# Sheet2.net
KiCad netlist of a schematic drawn in Altium Designer
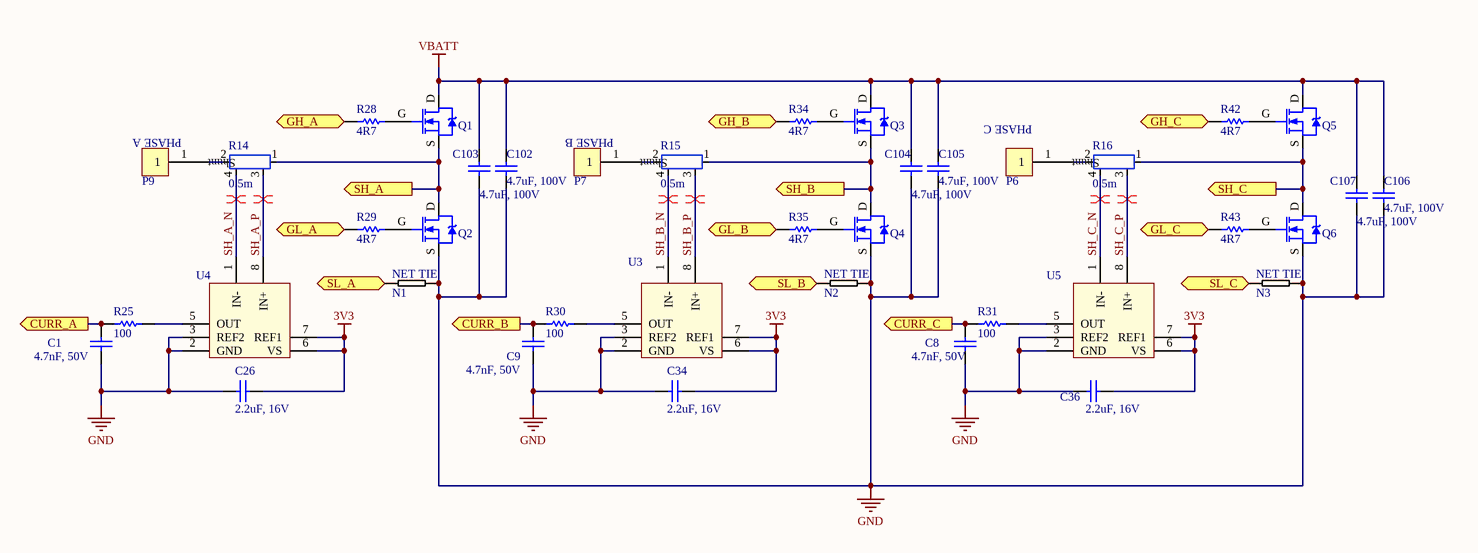
[diagram p0: Sheet2.SchDoc]

(export (version "E")
  (design (tool "Eeschema 10.0.6"))
  (components
    (comp (ref "C1")
      (value "4.7nF, 50V")
      (footprint "SMD-0603 Capacitor")
      (description "CAP 4.7n, 50V, 0603")
      (fields
        (field (name "MANUFACTURER PART NUMBER") "GRM39X472J50D")
        (field (name "MANUFACTURER") "Murata Electronics North America")
      )
      (libsource (lib "Master Data Link") (part "CAP"))
    )
    (comp (ref "C8")
      (value "4.7nF, 50V")
      (footprint "SMD-0603 Capacitor")
      (description "CAP 4.7n, 50V, 0603")
      (fields
        (field (name "MANUFACTURER PART NUMBER") "GRM39X472J50D")
        (field (name "MANUFACTURER") "Murata Electronics North America")
      )
      (libsource (lib "Master Data Link") (part "CAP"))
    )
    (comp (ref "C9")
      (value "4.7nF, 50V")
      (footprint "SMD-0603 Capacitor")
      (description "CAP 4.7n, 50V, 0603")
      (fields
        (field (name "MANUFACTURER PART NUMBER") "GRM39X472J50D")
        (field (name "MANUFACTURER") "Murata Electronics North America")
      )
      (libsource (lib "Master Data Link") (part "CAP"))
    )
    (comp (ref "C26")
      (value "2.2uF, 16V")
      (footprint "SMD-0603 Capacitor")
      (description "CAP 2.2u, 16V, 0603")
      (fields
        (field (name "MANUFACTURER PART NUMBER") "C1608X5R1C225M")
        (field (name "MANUFACTURER") "TDK Corporation")
      )
      (libsource (lib "Master Data Link") (part "CAP"))
    )
    (comp (ref "C34")
      (value "2.2uF, 16V")
      (footprint "SMD-0603 Capacitor")
      (description "CAP 2.2u, 16V, 0603")
      (fields
        (field (name "MANUFACTURER PART NUMBER") "C1608X5R1C225M")
        (field (name "MANUFACTURER") "TDK Corporation")
      )
      (libsource (lib "Master Data Link") (part "CAP"))
    )
    (comp (ref "C36")
      (value "2.2uF, 16V")
      (footprint "SMD-0603 Capacitor")
      (description "CAP 2.2u, 16V, 0603")
      (fields
        (field (name "MANUFACTURER PART NUMBER") "C1608X5R1C225M")
        (field (name "MANUFACTURER") "TDK Corporation")
      )
      (libsource (lib "Master Data Link") (part "CAP"))
    )
    (comp (ref "C102")
      (value "4.7uF, 100V")
      (footprint "SMD-1206 Capacitor")
      (description "4.7µF 100V Ceramic Capacitor X7S 1206")
      (fields
        (field (name "MANUFACTURER PART NUMBER") "12061Z475MAT2A")
        (field (name "MANUFACTURER") "AVX Corporation")
      )
      (libsource (lib "Master Data Link") (part "CAP"))
    )
    (comp (ref "C103")
      (value "4.7uF, 100V")
      (footprint "SMD-1206 Capacitor")
      (description "4.7µF 100V Ceramic Capacitor X7S 1206")
      (fields
        (field (name "MANUFACTURER PART NUMBER") "12061Z475MAT2A")
        (field (name "MANUFACTURER") "AVX Corporation")
      )
      (libsource (lib "Master Data Link") (part "CAP"))
    )
    (comp (ref "C104")
      (value "4.7uF, 100V")
      (footprint "SMD-1206 Capacitor")
      (description "4.7µF 100V Ceramic Capacitor X7S 1206")
      (fields
        (field (name "MANUFACTURER PART NUMBER") "12061Z475MAT2A")
        (field (name "MANUFACTURER") "AVX Corporation")
      )
      (libsource (lib "Master Data Link") (part "CAP"))
    )
    (comp (ref "C105")
      (value "4.7uF, 100V")
      (footprint "SMD-1206 Capacitor")
      (description "4.7µF 100V Ceramic Capacitor X7S 1206")
      (fields
        (field (name "MANUFACTURER PART NUMBER") "12061Z475MAT2A")
        (field (name "MANUFACTURER") "AVX Corporation")
      )
      (libsource (lib "Master Data Link") (part "CAP"))
    )
    (comp (ref "C106")
      (value "4.7uF, 100V")
      (footprint "SMD-1206 Capacitor")
      (description "4.7µF 100V Ceramic Capacitor X7S 1206")
      (fields
        (field (name "MANUFACTURER PART NUMBER") "12061Z475MAT2A")
        (field (name "MANUFACTURER") "AVX Corporation")
      )
      (libsource (lib "Master Data Link") (part "CAP"))
    )
    (comp (ref "C107")
      (value "4.7uF, 100V")
      (footprint "SMD-1206 Capacitor")
      (description "4.7µF 100V Ceramic Capacitor X7S 1206")
      (fields
        (field (name "MANUFACTURER PART NUMBER") "12061Z475MAT2A")
        (field (name "MANUFACTURER") "AVX Corporation")
      )
      (libsource (lib "Master Data Link") (part "CAP"))
    )
    (comp (ref "N1")
      (value "-")
      (footprint "NET TIE 12MM VIA")
      (libsource (lib "Master Data Link") (part "NET_TIE_1"))
    )
    (comp (ref "N2")
      (value "-")
      (footprint "NET TIE 12MM VIA")
      (libsource (lib "Master Data Link") (part "NET_TIE_1"))
    )
    (comp (ref "N3")
      (value "-")
      (footprint "NET TIE 12MM VIA")
      (libsource (lib "Master Data Link") (part "NET_TIE_1"))
    )
    (comp (ref "P6")
      (value "-")
      (footprint "PAD1")
      (description "SMD Power landing")
      (libsource (lib "Master Data Link") (part "CON1"))
    )
    (comp (ref "P7")
      (value "-")
      (footprint "PAD1")
      (description "SMD Power landing")
      (libsource (lib "Master Data Link") (part "CON1"))
    )
    (comp (ref "P9")
      (value "-")
      (footprint "PAD1")
      (description "SMD Power landing")
      (libsource (lib "Master Data Link") (part "CON1"))
    )
    (comp (ref "Q1")
      (value "MOSFET_N")
      (footprint "DIRECTFET_1")
      (description "MOSFET N-CH 60V 200A DIRECTFETL8")
      (fields
        (field (name "MANUFACTURER PART NUMBER") "IRF7749L1TRPBF")
        (field (name "MANUFACTURER") "Infineon Technologies Americas Corp")
      )
      (libsource (lib "Master Data Link") (part "MOSFET_N"))
    )
    (comp (ref "Q2")
      (value "MOSFET_N")
      (footprint "DIRECTFET_1")
      (description "MOSFET N-CH 60V 200A DIRECTFETL8")
      (fields
        (field (name "MANUFACTURER PART NUMBER") "IRF7749L1TRPBF")
        (field (name "MANUFACTURER") "Infineon Technologies Americas Corp")
      )
      (libsource (lib "Master Data Link") (part "MOSFET_N"))
    )
    (comp (ref "Q3")
      (value "MOSFET_N")
      (footprint "DIRECTFET_1")
      (description "MOSFET N-CH 60V 200A DIRECTFETL8")
      (fields
        (field (name "MANUFACTURER PART NUMBER") "IRF7749L1TRPBF")
        (field (name "MANUFACTURER") "Infineon Technologies Americas Corp")
      )
      (libsource (lib "Master Data Link") (part "MOSFET_N"))
    )
    (comp (ref "Q4")
      (value "MOSFET_N")
      (footprint "DIRECTFET_1")
      (description "MOSFET N-CH 60V 200A DIRECTFETL8")
      (fields
        (field (name "MANUFACTURER PART NUMBER") "IRF7749L1TRPBF")
        (field (name "MANUFACTURER") "Infineon Technologies Americas Corp")
      )
      (libsource (lib "Master Data Link") (part "MOSFET_N"))
    )
    (comp (ref "Q5")
      (value "MOSFET_N")
      (footprint "DIRECTFET_1")
      (description "MOSFET N-CH 60V 200A DIRECTFETL8")
      (fields
        (field (name "MANUFACTURER PART NUMBER") "IRF7749L1TRPBF")
        (field (name "MANUFACTURER") "Infineon Technologies Americas Corp")
      )
      (libsource (lib "Master Data Link") (part "MOSFET_N"))
    )
    (comp (ref "Q6")
      (value "MOSFET_N")
      (footprint "DIRECTFET_1")
      (description "MOSFET N-CH 60V 200A DIRECTFETL8")
      (fields
        (field (name "MANUFACTURER PART NUMBER") "IRF7749L1TRPBF")
        (field (name "MANUFACTURER") "Infineon Technologies Americas Corp")
      )
      (libsource (lib "Master Data Link") (part "MOSFET_N"))
    )
    (comp (ref "R14")
      (value "0.5m")
      (footprint "2512 Shunt")
      (description "RES SMD 500 UOHM 1% 6W 2512")
      (fields
        (field (name "MANUFACTURER PART NUMBER") "CSS2H-2512R-L500FE")
        (field (name "MANUFACTURER") "Bourn")
      )
      (libsource (lib "Master Data Link") (part "SHUNT_1"))
    )
    (comp (ref "R15")
      (value "0.5m")
      (footprint "2512 Shunt")
      (description "RES SMD 500 UOHM 1% 6W 2512")
      (fields
        (field (name "MANUFACTURER PART NUMBER") "CSS2H-2512R-L500FE")
        (field (name "MANUFACTURER") "Bourn")
      )
      (libsource (lib "Master Data Link") (part "SHUNT_1"))
    )
    (comp (ref "R16")
      (value "0.5m")
      (footprint "2512 Shunt")
      (description "RES SMD 500 UOHM 1% 6W 2512")
      (fields
        (field (name "MANUFACTURER PART NUMBER") "CSS2H-2512R-L500FE")
        (field (name "MANUFACTURER") "Bourn")
      )
      (libsource (lib "Master Data Link") (part "SHUNT_1"))
    )
    (comp (ref "R25")
      (value "100")
      (footprint "SMD-0603 Resistor")
      (description "R 100ohm, 0603")
      (fields
        (field (name "MANUFACTURER PART NUMBER") "RK73H1JTTD1000F")
        (field (name "MANUFACTURER") "KOA Speer")
      )
      (libsource (lib "Master Data Link") (part "RES"))
    )
    (comp (ref "R28")
      (value "4R7")
      (footprint "SMD-0603 Resistor")
      (description "R 4.7ohm, 0603")
      (fields
        (field (name "MANUFACTURER PART NUMBER") "RK73H1JTTD4R70F")
        (field (name "MANUFACTURER") "KOA Speer")
      )
      (libsource (lib "Master Data Link") (part "RES"))
    )
    (comp (ref "R29")
      (value "4R7")
      (footprint "SMD-0603 Resistor")
      (description "R 4.7ohm, 0603")
      (fields
        (field (name "MANUFACTURER PART NUMBER") "RK73H1JTTD4R70F")
        (field (name "MANUFACTURER") "KOA Speer")
      )
      (libsource (lib "Master Data Link") (part "RES"))
    )
    (comp (ref "R30")
      (value "100")
      (footprint "SMD-0603 Resistor")
      (description "R 100ohm, 0603")
      (fields
        (field (name "MANUFACTURER PART NUMBER") "RK73H1JTTD1000F")
        (field (name "MANUFACTURER") "KOA Speer")
      )
      (libsource (lib "Master Data Link") (part "RES"))
    )
    (comp (ref "R31")
      (value "100")
      (footprint "SMD-0603 Resistor")
      (description "R 100ohm, 0603")
      (fields
        (field (name "MANUFACTURER PART NUMBER") "RK73H1JTTD1000F")
        (field (name "MANUFACTURER") "KOA Speer")
      )
      (libsource (lib "Master Data Link") (part "RES"))
    )
    (comp (ref "R34")
      (value "4R7")
      (footprint "SMD-0603 Resistor")
      (description "R 4.7ohm, 0603")
      (fields
        (field (name "MANUFACTURER PART NUMBER") "RK73H1JTTD4R70F")
        (field (name "MANUFACTURER") "KOA Speer")
      )
      (libsource (lib "Master Data Link") (part "RES"))
    )
    (comp (ref "R35")
      (value "4R7")
      (footprint "SMD-0603 Resistor")
      (description "R 4.7ohm, 0603")
      (fields
        (field (name "MANUFACTURER PART NUMBER") "RK73H1JTTD4R70F")
        (field (name "MANUFACTURER") "KOA Speer")
      )
      (libsource (lib "Master Data Link") (part "RES"))
    )
    (comp (ref "R42")
      (value "4R7")
      (footprint "SMD-0603 Resistor")
      (description "R 4.7ohm, 0603")
      (fields
        (field (name "MANUFACTURER PART NUMBER") "RK73H1JTTD4R70F")
        (field (name "MANUFACTURER") "KOA Speer")
      )
      (libsource (lib "Master Data Link") (part "RES"))
    )
    (comp (ref "R43")
      (value "4R7")
      (footprint "SMD-0603 Resistor")
      (description "R 4.7ohm, 0603")
      (fields
        (field (name "MANUFACTURER PART NUMBER") "RK73H1JTTD4R70F")
        (field (name "MANUFACTURER") "KOA Speer")
      )
      (libsource (lib "Master Data Link") (part "RES"))
    )
    (comp (ref "U3")
      (value "AD8418")
      (footprint "MSOP-8")
      (description "IC OPAMP CURR SENSE 8MSOP")
      (fields
        (field (name "MANUFACTURER PART NUMBER") "AD8418AWHRMZ")
        (field (name "MANUFACTURER") "Analog Devices Inc.")
      )
      (libsource (lib "Master Data Link") (part "AD8418"))
    )
    (comp (ref "U4")
      (value "AD8418")
      (footprint "MSOP-8")
      (description "IC OPAMP CURR SENSE 8MSOP")
      (fields
        (field (name "MANUFACTURER PART NUMBER") "AD8418AWHRMZ")
        (field (name "MANUFACTURER") "Analog Devices Inc.")
      )
      (libsource (lib "Master Data Link") (part "AD8418"))
    )
    (comp (ref "U5")
      (value "AD8418")
      (footprint "MSOP-8")
      (description "IC OPAMP CURR SENSE 8MSOP")
      (fields
        (field (name "MANUFACTURER PART NUMBER") "AD8418AWHRMZ")
        (field (name "MANUFACTURER") "Analog Devices Inc.")
      )
      (libsource (lib "Master Data Link") (part "AD8418"))
    )
  )
  (nets
    (net (code "1") (name "/CURR_A") (class "Default")
      (node (ref "C1") (pin "2") (pinfunction "2_2") (pintype "passive"))
      (node (ref "R25") (pin "1") (pinfunction "1_1") (pintype "passive"))
    )
    (net (code "2") (name "/CURR_B") (class "Default")
      (node (ref "C9") (pin "2") (pinfunction "2_2") (pintype "passive"))
      (node (ref "R30") (pin "1") (pinfunction "1_1") (pintype "passive"))
    )
    (net (code "3") (name "/CURR_C") (class "Default")
      (node (ref "C8") (pin "2") (pinfunction "2_2") (pintype "passive"))
      (node (ref "R31") (pin "1") (pinfunction "1_1") (pintype "passive"))
    )
    (net (code "4") (name "/GH_A") (class "Default")
      (node (ref "R28") (pin "1") (pinfunction "1_1") (pintype "passive"))
    )
    (net (code "5") (name "/GH_B") (class "Default")
      (node (ref "R34") (pin "1") (pinfunction "1_1") (pintype "passive"))
    )
    (net (code "6") (name "/GH_C") (class "Default")
      (node (ref "R42") (pin "1") (pinfunction "1_1") (pintype "passive"))
    )
    (net (code "7") (name "/GL_A") (class "Default")
      (node (ref "R29") (pin "1") (pinfunction "1_1") (pintype "passive"))
    )
    (net (code "8") (name "/GL_B") (class "Default")
      (node (ref "R35") (pin "1") (pinfunction "1_1") (pintype "passive"))
    )
    (net (code "9") (name "/GL_C") (class "Default")
      (node (ref "R43") (pin "1") (pinfunction "1_1") (pintype "passive"))
    )
    (net (code "10") (name "/SH_A") (class "Default")
      (node (ref "Q1") (pin "S") (pinfunction "S_S") (pintype "passive"))
      (node (ref "Q2") (pin "D") (pinfunction "D_D") (pintype "passive"))
      (node (ref "R14") (pin "1") (pinfunction "1_1") (pintype "passive"))
    )
    (net (code "11") (name "/SH_A_N") (class "Default")
      (node (ref "R14") (pin "4") (pinfunction "3_4") (pintype "passive"))
      (node (ref "U4") (pin "1") (pinfunction "IN-_1") (pintype "passive"))
    )
    (net (code "12") (name "/SH_A_P") (class "Default")
      (node (ref "R14") (pin "3") (pinfunction "2_3") (pintype "passive"))
      (node (ref "U4") (pin "8") (pinfunction "IN+_8") (pintype "passive"))
    )
    (net (code "13") (name "/SH_B") (class "Default")
      (node (ref "Q3") (pin "S") (pinfunction "S_S") (pintype "passive"))
      (node (ref "Q4") (pin "D") (pinfunction "D_D") (pintype "passive"))
      (node (ref "R15") (pin "1") (pinfunction "1_1") (pintype "passive"))
    )
    (net (code "14") (name "/SH_B_N") (class "Default")
      (node (ref "R15") (pin "4") (pinfunction "3_4") (pintype "passive"))
      (node (ref "U3") (pin "1") (pinfunction "IN-_1") (pintype "passive"))
    )
    (net (code "15") (name "/SH_B_P") (class "Default")
      (node (ref "R15") (pin "3") (pinfunction "2_3") (pintype "passive"))
      (node (ref "U3") (pin "8") (pinfunction "IN+_8") (pintype "passive"))
    )
    (net (code "16") (name "/SH_C") (class "Default")
      (node (ref "Q5") (pin "S") (pinfunction "S_S") (pintype "passive"))
      (node (ref "Q6") (pin "D") (pinfunction "D_D") (pintype "passive"))
      (node (ref "R16") (pin "1") (pinfunction "1_1") (pintype "passive"))
    )
    (net (code "17") (name "/SH_C_N") (class "Default")
      (node (ref "R16") (pin "4") (pinfunction "3_4") (pintype "passive"))
      (node (ref "U5") (pin "1") (pinfunction "IN-_1") (pintype "passive"))
    )
    (net (code "18") (name "/SH_C_P") (class "Default")
      (node (ref "R16") (pin "3") (pinfunction "2_3") (pintype "passive"))
      (node (ref "U5") (pin "8") (pinfunction "IN+_8") (pintype "passive"))
    )
    (net (code "19") (name "/SL_A") (class "Default")
      (node (ref "N1") (pin "1") (pinfunction "1_1") (pintype "passive"))
    )
    (net (code "20") (name "/SL_B") (class "Default")
      (node (ref "N2") (pin "1") (pinfunction "1_1") (pintype "passive"))
    )
    (net (code "21") (name "/SL_C") (class "Default")
      (node (ref "N3") (pin "1") (pinfunction "1_1") (pintype "passive"))
    )
    (net (code "22") (name "3V3") (class "Default")
      (node (ref "C26") (pin "2") (pinfunction "2_2") (pintype "passive"))
      (node (ref "C34") (pin "2") (pinfunction "2_2") (pintype "passive"))
      (node (ref "C36") (pin "2") (pinfunction "2_2") (pintype "passive"))
      (node (ref "U3") (pin "6") (pinfunction "VS_6") (pintype "passive"))
      (node (ref "U3") (pin "7") (pinfunction "REF1_7") (pintype "passive"))
      (node (ref "U4") (pin "6") (pinfunction "VS_6") (pintype "passive"))
      (node (ref "U4") (pin "7") (pinfunction "REF1_7") (pintype "passive"))
      (node (ref "U5") (pin "6") (pinfunction "VS_6") (pintype "passive"))
      (node (ref "U5") (pin "7") (pinfunction "REF1_7") (pintype "passive"))
    )
    (net (code "23") (name "GND") (class "Default")
      (node (ref "C1") (pin "1") (pinfunction "1_1") (pintype "passive"))
      (node (ref "C102") (pin "2") (pinfunction "2_2") (pintype "passive"))
      (node (ref "C103") (pin "2") (pinfunction "2_2") (pintype "passive"))
      (node (ref "C104") (pin "1") (pinfunction "1_1") (pintype "passive"))
      (node (ref "C105") (pin "1") (pinfunction "1_1") (pintype "passive"))
      (node (ref "C106") (pin "2") (pinfunction "2_2") (pintype "passive"))
      (node (ref "C107") (pin "2") (pinfunction "2_2") (pintype "passive"))
      (node (ref "C26") (pin "1") (pinfunction "1_1") (pintype "passive"))
      (node (ref "C34") (pin "1") (pinfunction "1_1") (pintype "passive"))
      (node (ref "C36") (pin "1") (pinfunction "1_1") (pintype "passive"))
      (node (ref "C8") (pin "1") (pinfunction "1_1") (pintype "passive"))
      (node (ref "C9") (pin "1") (pinfunction "1_1") (pintype "passive"))
      (node (ref "N1") (pin "2") (pinfunction "2_2") (pintype "passive"))
      (node (ref "N2") (pin "2") (pinfunction "2_2") (pintype "passive"))
      (node (ref "N3") (pin "2") (pinfunction "2_2") (pintype "passive"))
      (node (ref "Q2") (pin "S") (pinfunction "S_S") (pintype "passive"))
      (node (ref "Q4") (pin "S") (pinfunction "S_S") (pintype "passive"))
      (node (ref "Q6") (pin "S") (pinfunction "S_S") (pintype "passive"))
      (node (ref "U3") (pin "2") (pinfunction "GND_2") (pintype "passive"))
      (node (ref "U3") (pin "3") (pinfunction "REF2_3") (pintype "passive"))
      (node (ref "U4") (pin "2") (pinfunction "GND_2") (pintype "passive"))
      (node (ref "U4") (pin "3") (pinfunction "REF2_3") (pintype "passive"))
      (node (ref "U5") (pin "2") (pinfunction "GND_2") (pintype "passive"))
      (node (ref "U5") (pin "3") (pinfunction "REF2_3") (pintype "passive"))
    )
    (net (code "24") (name "Net-(P6-Pad1)") (class "Default")
      (node (ref "P6") (pin "1") (pinfunction "1_1") (pintype "passive"))
      (node (ref "R16") (pin "2") (pinfunction "2_2") (pintype "passive"))
    )
    (net (code "25") (name "Net-(P7-Pad1)") (class "Default")
      (node (ref "P7") (pin "1") (pinfunction "1_1") (pintype "passive"))
      (node (ref "R15") (pin "2") (pinfunction "2_2") (pintype "passive"))
    )
    (net (code "26") (name "Net-(P9-Pad1)") (class "Default")
      (node (ref "P9") (pin "1") (pinfunction "1_1") (pintype "passive"))
      (node (ref "R14") (pin "2") (pinfunction "2_2") (pintype "passive"))
    )
    (net (code "27") (name "Net-(Q1-PadG)") (class "Default")
      (node (ref "Q1") (pin "G") (pinfunction "G_G") (pintype "passive"))
      (node (ref "R28") (pin "2") (pinfunction "2_2") (pintype "passive"))
    )
    (net (code "28") (name "Net-(Q2-PadG)") (class "Default")
      (node (ref "Q2") (pin "G") (pinfunction "G_G") (pintype "passive"))
      (node (ref "R29") (pin "2") (pinfunction "2_2") (pintype "passive"))
    )
    (net (code "29") (name "Net-(Q3-PadG)") (class "Default")
      (node (ref "Q3") (pin "G") (pinfunction "G_G") (pintype "passive"))
      (node (ref "R34") (pin "2") (pinfunction "2_2") (pintype "passive"))
    )
    (net (code "30") (name "Net-(Q4-PadG)") (class "Default")
      (node (ref "Q4") (pin "G") (pinfunction "G_G") (pintype "passive"))
      (node (ref "R35") (pin "2") (pinfunction "2_2") (pintype "passive"))
    )
    (net (code "31") (name "Net-(Q5-PadG)") (class "Default")
      (node (ref "Q5") (pin "G") (pinfunction "G_G") (pintype "passive"))
      (node (ref "R42") (pin "2") (pinfunction "2_2") (pintype "passive"))
    )
    (net (code "32") (name "Net-(Q6-PadG)") (class "Default")
      (node (ref "Q6") (pin "G") (pinfunction "G_G") (pintype "passive"))
      (node (ref "R43") (pin "2") (pinfunction "2_2") (pintype "passive"))
    )
    (net (code "33") (name "Net-(U3-OUT)") (class "Default")
      (node (ref "R30") (pin "2") (pinfunction "2_2") (pintype "passive"))
      (node (ref "U3") (pin "5") (pinfunction "OUT_5") (pintype "passive"))
    )
    (net (code "34") (name "Net-(U4-OUT)") (class "Default")
      (node (ref "R25") (pin "2") (pinfunction "2_2") (pintype "passive"))
      (node (ref "U4") (pin "5") (pinfunction "OUT_5") (pintype "passive"))
    )
    (net (code "35") (name "Net-(U5-OUT)") (class "Default")
      (node (ref "R31") (pin "2") (pinfunction "2_2") (pintype "passive"))
      (node (ref "U5") (pin "5") (pinfunction "OUT_5") (pintype "passive"))
    )
    (net (code "36") (name "VBATT") (class "Default")
      (node (ref "C102") (pin "1") (pinfunction "1_1") (pintype "passive"))
      (node (ref "C103") (pin "1") (pinfunction "1_1") (pintype "passive"))
      (node (ref "C104") (pin "2") (pinfunction "2_2") (pintype "passive"))
      (node (ref "C105") (pin "2") (pinfunction "2_2") (pintype "passive"))
      (node (ref "C106") (pin "1") (pinfunction "1_1") (pintype "passive"))
      (node (ref "C107") (pin "1") (pinfunction "1_1") (pintype "passive"))
      (node (ref "Q1") (pin "D") (pinfunction "D_D") (pintype "passive"))
      (node (ref "Q3") (pin "D") (pinfunction "D_D") (pintype "passive"))
      (node (ref "Q5") (pin "D") (pinfunction "D_D") (pintype "passive"))
    )
  )
)
